# SSD_M_2_B-Key.net
KiCad netlist of a schematic drawn in Altium Designer
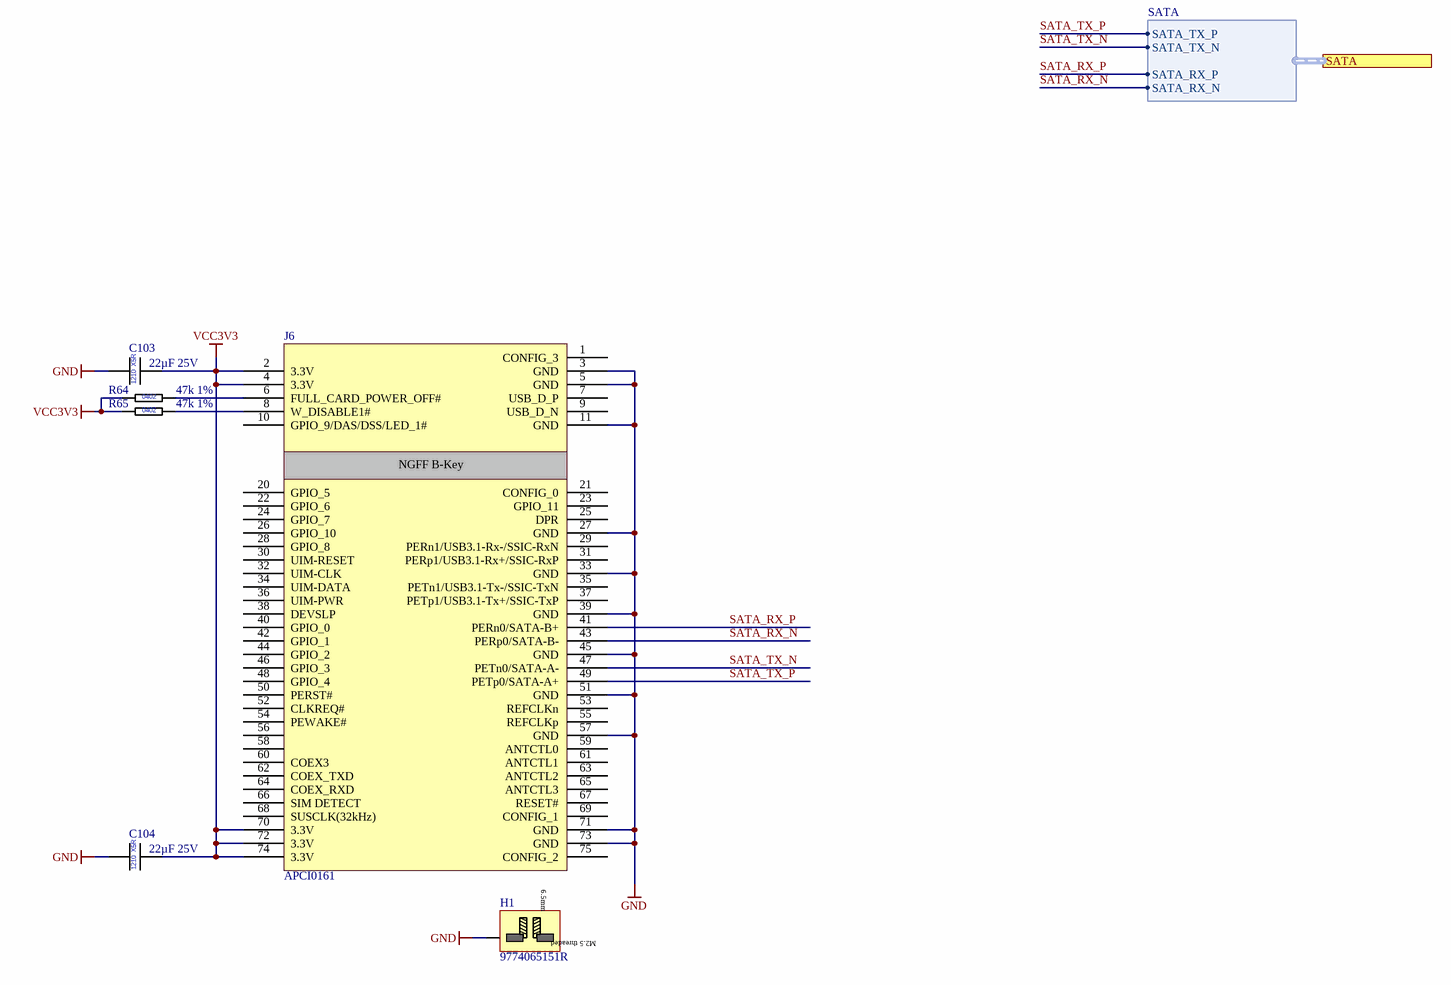
[diagram p0: SSD M.2_B-Key.SchDoc]

(export (version "E")
  (design (tool "Eeschema 10.0.6"))
  (components
    (comp (ref "C103")
      (value "22µF 25V")
      (footprint "Cap:CAP_1210")
      (description "Multilayer Ceramic Capacitors MLCC - SMD/SMT 1210 25VDC")
      (libsource (lib "Cap") (part "CAP_1210_22µF_25V"))
    )
    (comp (ref "C104")
      (value "22µF 25V")
      (footprint "Cap:CAP_1210")
      (description "Multilayer Ceramic Capacitors MLCC - SMD/SMT 1210 25VDC")
      (libsource (lib "Cap") (part "CAP_1210_22µF_25V"))
    )
    (comp (ref "H1")
      (value "9774065151R")
      (footprint "Electro_Mech:9774065151R")
      (description "Würth Standoff M2.5 h:6.5mm 9774065151R")
      (libsource (lib "Electro_Mech") (part "Würth Standoff M2.5 h{colon}6.5mm"))
    )
    (comp (ref "J6")
      (value "APCI0161")
      (footprint "conn:APCI0161-P001A")
      (description "NGFF B-Key Card Edge Connector 8.5mm Height")
      (libsource (lib "Conn") (part "APCI0161-NGFF B-Key Card Edge Connector 8.5mm Height"))
    )
    (comp (ref "R64")
      (value "47k 1%")
      (footprint "Res:RES_0402_L")
      (description "Thick Film Resistors - SMD 47kOhm 1%")
      (libsource (lib "Res") (part "RES_0402_47k_1%"))
    )
    (comp (ref "R65")
      (value "47k 1%")
      (footprint "Res:RES_0402_L")
      (description "Thick Film Resistors - SMD 47kOhm 1%")
      (libsource (lib "Res") (part "RES_0402_47k_1%"))
    )
  )
  (nets
    (net (code "2") (name "/SATA_RX_N") (class "Default")
      (node (ref "J6") (pin "43") (pinfunction "PERp0/SATA-B-_43") (pintype "passive"))
    )
    (net (code "3") (name "/SATA_RX_P") (class "Default")
      (node (ref "J6") (pin "41") (pinfunction "PERn0/SATA-B+_41") (pintype "passive"))
    )
    (net (code "4") (name "/SATA_TX_N") (class "Default")
      (node (ref "J6") (pin "47") (pinfunction "PETn0/SATA-A-_47") (pintype "passive"))
    )
    (net (code "5") (name "/SATA_TX_P") (class "Default")
      (node (ref "J6") (pin "49") (pinfunction "PETp0/SATA-A+_49") (pintype "passive"))
    )
    (net (code "7") (name "GND") (class "Default")
      (node (ref "C103") (pin "1") (pinfunction "1_1") (pintype "passive"))
      (node (ref "C104") (pin "1") (pinfunction "1_1") (pintype "passive"))
      (node (ref "H1") (pin "1") (pinfunction "1_1") (pintype "passive"))
      (node (ref "J6") (pin "11") (pinfunction "GND_11") (pintype "passive"))
      (node (ref "J6") (pin "27") (pinfunction "GND_27") (pintype "passive"))
      (node (ref "J6") (pin "3") (pinfunction "GND_3") (pintype "passive"))
      (node (ref "J6") (pin "33") (pinfunction "GND_33") (pintype "passive"))
      (node (ref "J6") (pin "39") (pinfunction "GND_39") (pintype "passive"))
      (node (ref "J6") (pin "45") (pinfunction "GND_45") (pintype "passive"))
      (node (ref "J6") (pin "5") (pinfunction "GND_5") (pintype "passive"))
      (node (ref "J6") (pin "51") (pinfunction "GND_51") (pintype "passive"))
      (node (ref "J6") (pin "57") (pinfunction "GND_57") (pintype "passive"))
      (node (ref "J6") (pin "71") (pinfunction "GND_71") (pintype "passive"))
      (node (ref "J6") (pin "73") (pinfunction "GND_73") (pintype "passive"))
    )
    (net (code "8") (name "Net-(J6-FULL_CARD_POWER_OFF#)") (class "Default")
      (node (ref "J6") (pin "6") (pinfunction "FULL_CARD_POWER_OFF#_6") (pintype "passive"))
      (node (ref "R64") (pin "2") (pinfunction "2_2") (pintype "passive"))
    )
    (net (code "9") (name "Net-(J6-W_DISABLE1#)") (class "Default")
      (node (ref "J6") (pin "8") (pinfunction "W_DISABLE1#_8") (pintype "passive"))
      (node (ref "R65") (pin "2") (pinfunction "2_2") (pintype "passive"))
    )
    (net (code "10") (name "VCC3V3") (class "Default")
      (node (ref "C103") (pin "2") (pinfunction "2_2") (pintype "passive"))
      (node (ref "C104") (pin "2") (pinfunction "2_2") (pintype "passive"))
      (node (ref "J6") (pin "2") (pinfunction "3.3V_2") (pintype "passive"))
      (node (ref "J6") (pin "4") (pinfunction "3.3V_4") (pintype "passive"))
      (node (ref "J6") (pin "70") (pinfunction "3.3V_70") (pintype "passive"))
      (node (ref "J6") (pin "72") (pinfunction "3.3V_72") (pintype "passive"))
      (node (ref "J6") (pin "74") (pinfunction "3.3V_74") (pintype "passive"))
      (node (ref "R64") (pin "1") (pinfunction "1_1") (pintype "passive"))
      (node (ref "R65") (pin "1") (pinfunction "1_1") (pintype "passive"))
    )
    (net (code "11") (name "unconnected-(J6-ANTCTL0-Pad59)") (class "Default")
      (node (ref "J6") (pin "59") (pinfunction "ANTCTL0_59") (pintype "passive"))
    )
    (net (code "12") (name "unconnected-(J6-ANTCTL1-Pad61)") (class "Default")
      (node (ref "J6") (pin "61") (pinfunction "ANTCTL1_61") (pintype "passive"))
    )
    (net (code "13") (name "unconnected-(J6-ANTCTL2-Pad63)") (class "Default")
      (node (ref "J6") (pin "63") (pinfunction "ANTCTL2_63") (pintype "passive"))
    )
    (net (code "14") (name "unconnected-(J6-ANTCTL3-Pad65)") (class "Default")
      (node (ref "J6") (pin "65") (pinfunction "ANTCTL3_65") (pintype "passive"))
    )
    (net (code "15") (name "unconnected-(J6-CLKREQ#-Pad52)") (class "Default")
      (node (ref "J6") (pin "52") (pinfunction "CLKREQ#_52") (pintype "passive"))
    )
    (net (code "16") (name "unconnected-(J6-COEX3-Pad60)") (class "Default")
      (node (ref "J6") (pin "60") (pinfunction "COEX3_60") (pintype "passive"))
    )
    (net (code "17") (name "unconnected-(J6-COEX_RXD-Pad64)") (class "Default")
      (node (ref "J6") (pin "64") (pinfunction "COEX_RXD_64") (pintype "passive"))
    )
    (net (code "18") (name "unconnected-(J6-COEX_TXD-Pad62)") (class "Default")
      (node (ref "J6") (pin "62") (pinfunction "COEX_TXD_62") (pintype "passive"))
    )
    (net (code "19") (name "unconnected-(J6-CONFIG_0-Pad21)") (class "Default")
      (node (ref "J6") (pin "21") (pinfunction "CONFIG_0_21") (pintype "passive"))
    )
    (net (code "20") (name "unconnected-(J6-CONFIG_1-Pad69)") (class "Default")
      (node (ref "J6") (pin "69") (pinfunction "CONFIG_1_69") (pintype "passive"))
    )
    (net (code "21") (name "unconnected-(J6-CONFIG_2-Pad75)") (class "Default")
      (node (ref "J6") (pin "75") (pinfunction "CONFIG_2_75") (pintype "passive"))
    )
    (net (code "22") (name "unconnected-(J6-CONFIG_3-Pad1)") (class "Default")
      (node (ref "J6") (pin "1") (pinfunction "CONFIG_3_1") (pintype "passive"))
    )
    (net (code "23") (name "unconnected-(J6-DEVSLP-Pad38)") (class "Default")
      (node (ref "J6") (pin "38") (pinfunction "DEVSLP_38") (pintype "passive"))
    )
    (net (code "24") (name "unconnected-(J6-DPR-Pad25)") (class "Default")
      (node (ref "J6") (pin "25") (pinfunction "DPR_25") (pintype "passive"))
    )
    (net (code "25") (name "unconnected-(J6-GPIO_0-Pad40)") (class "Default")
      (node (ref "J6") (pin "40") (pinfunction "GPIO_0_40") (pintype "passive"))
    )
    (net (code "26") (name "unconnected-(J6-GPIO_1-Pad42)") (class "Default")
      (node (ref "J6") (pin "42") (pinfunction "GPIO_1_42") (pintype "passive"))
    )
    (net (code "27") (name "unconnected-(J6-GPIO_2-Pad44)") (class "Default")
      (node (ref "J6") (pin "44") (pinfunction "GPIO_2_44") (pintype "passive"))
    )
    (net (code "28") (name "unconnected-(J6-GPIO_3-Pad46)") (class "Default")
      (node (ref "J6") (pin "46") (pinfunction "GPIO_3_46") (pintype "passive"))
    )
    (net (code "29") (name "unconnected-(J6-GPIO_4-Pad48)") (class "Default")
      (node (ref "J6") (pin "48") (pinfunction "GPIO_4_48") (pintype "passive"))
    )
    (net (code "30") (name "unconnected-(J6-GPIO_5-Pad20)") (class "Default")
      (node (ref "J6") (pin "20") (pinfunction "GPIO_5_20") (pintype "passive"))
    )
    (net (code "31") (name "unconnected-(J6-GPIO_6-Pad22)") (class "Default")
      (node (ref "J6") (pin "22") (pinfunction "GPIO_6_22") (pintype "passive"))
    )
    (net (code "32") (name "unconnected-(J6-GPIO_7-Pad24)") (class "Default")
      (node (ref "J6") (pin "24") (pinfunction "GPIO_7_24") (pintype "passive"))
    )
    (net (code "33") (name "unconnected-(J6-GPIO_8-Pad28)") (class "Default")
      (node (ref "J6") (pin "28") (pinfunction "GPIO_8_28") (pintype "passive"))
    )
    (net (code "34") (name "unconnected-(J6-GPIO_9{slash}DAS{slash}DSS{slash}LED_1#-Pad10)") (class "Default")
      (node (ref "J6") (pin "10") (pinfunction "GPIO_9/DAS/DSS/LED_1#_10") (pintype "passive"))
    )
    (net (code "35") (name "unconnected-(J6-GPIO_10-Pad26)") (class "Default")
      (node (ref "J6") (pin "26") (pinfunction "GPIO_10_26") (pintype "passive"))
    )
    (net (code "36") (name "unconnected-(J6-GPIO_11-Pad23)") (class "Default")
      (node (ref "J6") (pin "23") (pinfunction "GPIO_11_23") (pintype "passive"))
    )
    (net (code "37") (name "unconnected-(J6-PERST#-Pad50)") (class "Default")
      (node (ref "J6") (pin "50") (pinfunction "PERST#_50") (pintype "passive"))
    )
    (net (code "38") (name "unconnected-(J6-PERn1{slash}USB3.1-Rx-{slash}SSIC-RxN-Pad29)") (class "Default")
      (node (ref "J6") (pin "29") (pinfunction "PERn1/USB3.1-Rx-/SSIC-RxN_29") (pintype "passive"))
    )
    (net (code "39") (name "unconnected-(J6-PERp1{slash}USB3.1-Rx+{slash}SSIC-RxP-Pad31)") (class "Default")
      (node (ref "J6") (pin "31") (pinfunction "PERp1/USB3.1-Rx+/SSIC-RxP_31") (pintype "passive"))
    )
    (net (code "40") (name "unconnected-(J6-PETn1{slash}USB3.1-Tx-{slash}SSIC-TxN-Pad35)") (class "Default")
      (node (ref "J6") (pin "35") (pinfunction "PETn1/USB3.1-Tx-/SSIC-TxN_35") (pintype "passive"))
    )
    (net (code "41") (name "unconnected-(J6-PETp1{slash}USB3.1-Tx+{slash}SSIC-TxP-Pad37)") (class "Default")
      (node (ref "J6") (pin "37") (pinfunction "PETp1/USB3.1-Tx+/SSIC-TxP_37") (pintype "passive"))
    )
    (net (code "42") (name "unconnected-(J6-PEWAKE#-Pad54)") (class "Default")
      (node (ref "J6") (pin "54") (pinfunction "PEWAKE#_54") (pintype "passive"))
    )
    (net (code "43") (name "unconnected-(J6-Pad56)") (class "Default")
      (node (ref "J6") (pin "56") (pintype "passive"))
    )
    (net (code "44") (name "unconnected-(J6-Pad58)") (class "Default")
      (node (ref "J6") (pin "58") (pintype "passive"))
    )
    (net (code "45") (name "unconnected-(J6-REFCLKn-Pad53)") (class "Default")
      (node (ref "J6") (pin "53") (pinfunction "REFCLKn_53") (pintype "passive"))
    )
    (net (code "46") (name "unconnected-(J6-REFCLKp-Pad55)") (class "Default")
      (node (ref "J6") (pin "55") (pinfunction "REFCLKp_55") (pintype "passive"))
    )
    (net (code "47") (name "unconnected-(J6-RESET#-Pad67)") (class "Default")
      (node (ref "J6") (pin "67") (pinfunction "RESET#_67") (pintype "passive"))
    )
    (net (code "48") (name "unconnected-(J6-SIM_DETECT-Pad66)") (class "Default")
      (node (ref "J6") (pin "66") (pinfunction "SIM_DETECT_66") (pintype "passive"))
    )
    (net (code "49") (name "unconnected-(J6-SUSCLK(32kHz)-Pad68)") (class "Default")
      (node (ref "J6") (pin "68") (pinfunction "SUSCLK(32kHz)_68") (pintype "passive"))
    )
    (net (code "50") (name "unconnected-(J6-UIM-CLK-Pad32)") (class "Default")
      (node (ref "J6") (pin "32") (pinfunction "UIM-CLK_32") (pintype "passive"))
    )
    (net (code "51") (name "unconnected-(J6-UIM-DATA-Pad34)") (class "Default")
      (node (ref "J6") (pin "34") (pinfunction "UIM-DATA_34") (pintype "passive"))
    )
    (net (code "52") (name "unconnected-(J6-UIM-PWR-Pad36)") (class "Default")
      (node (ref "J6") (pin "36") (pinfunction "UIM-PWR_36") (pintype "passive"))
    )
    (net (code "53") (name "unconnected-(J6-UIM-RESET-Pad30)") (class "Default")
      (node (ref "J6") (pin "30") (pinfunction "UIM-RESET_30") (pintype "passive"))
    )
    (net (code "54") (name "unconnected-(J6-USB_D_N-Pad9)") (class "Default")
      (node (ref "J6") (pin "9") (pinfunction "USB_D_N_9") (pintype "passive"))
    )
    (net (code "55") (name "unconnected-(J6-USB_D_P-Pad7)") (class "Default")
      (node (ref "J6") (pin "7") (pinfunction "USB_D_P_7") (pintype "passive"))
    )
  )
)
